# SN74HC165_Shift-In_Breakout-v12.net
KiCad netlist of a schematic drawn in EAGLE
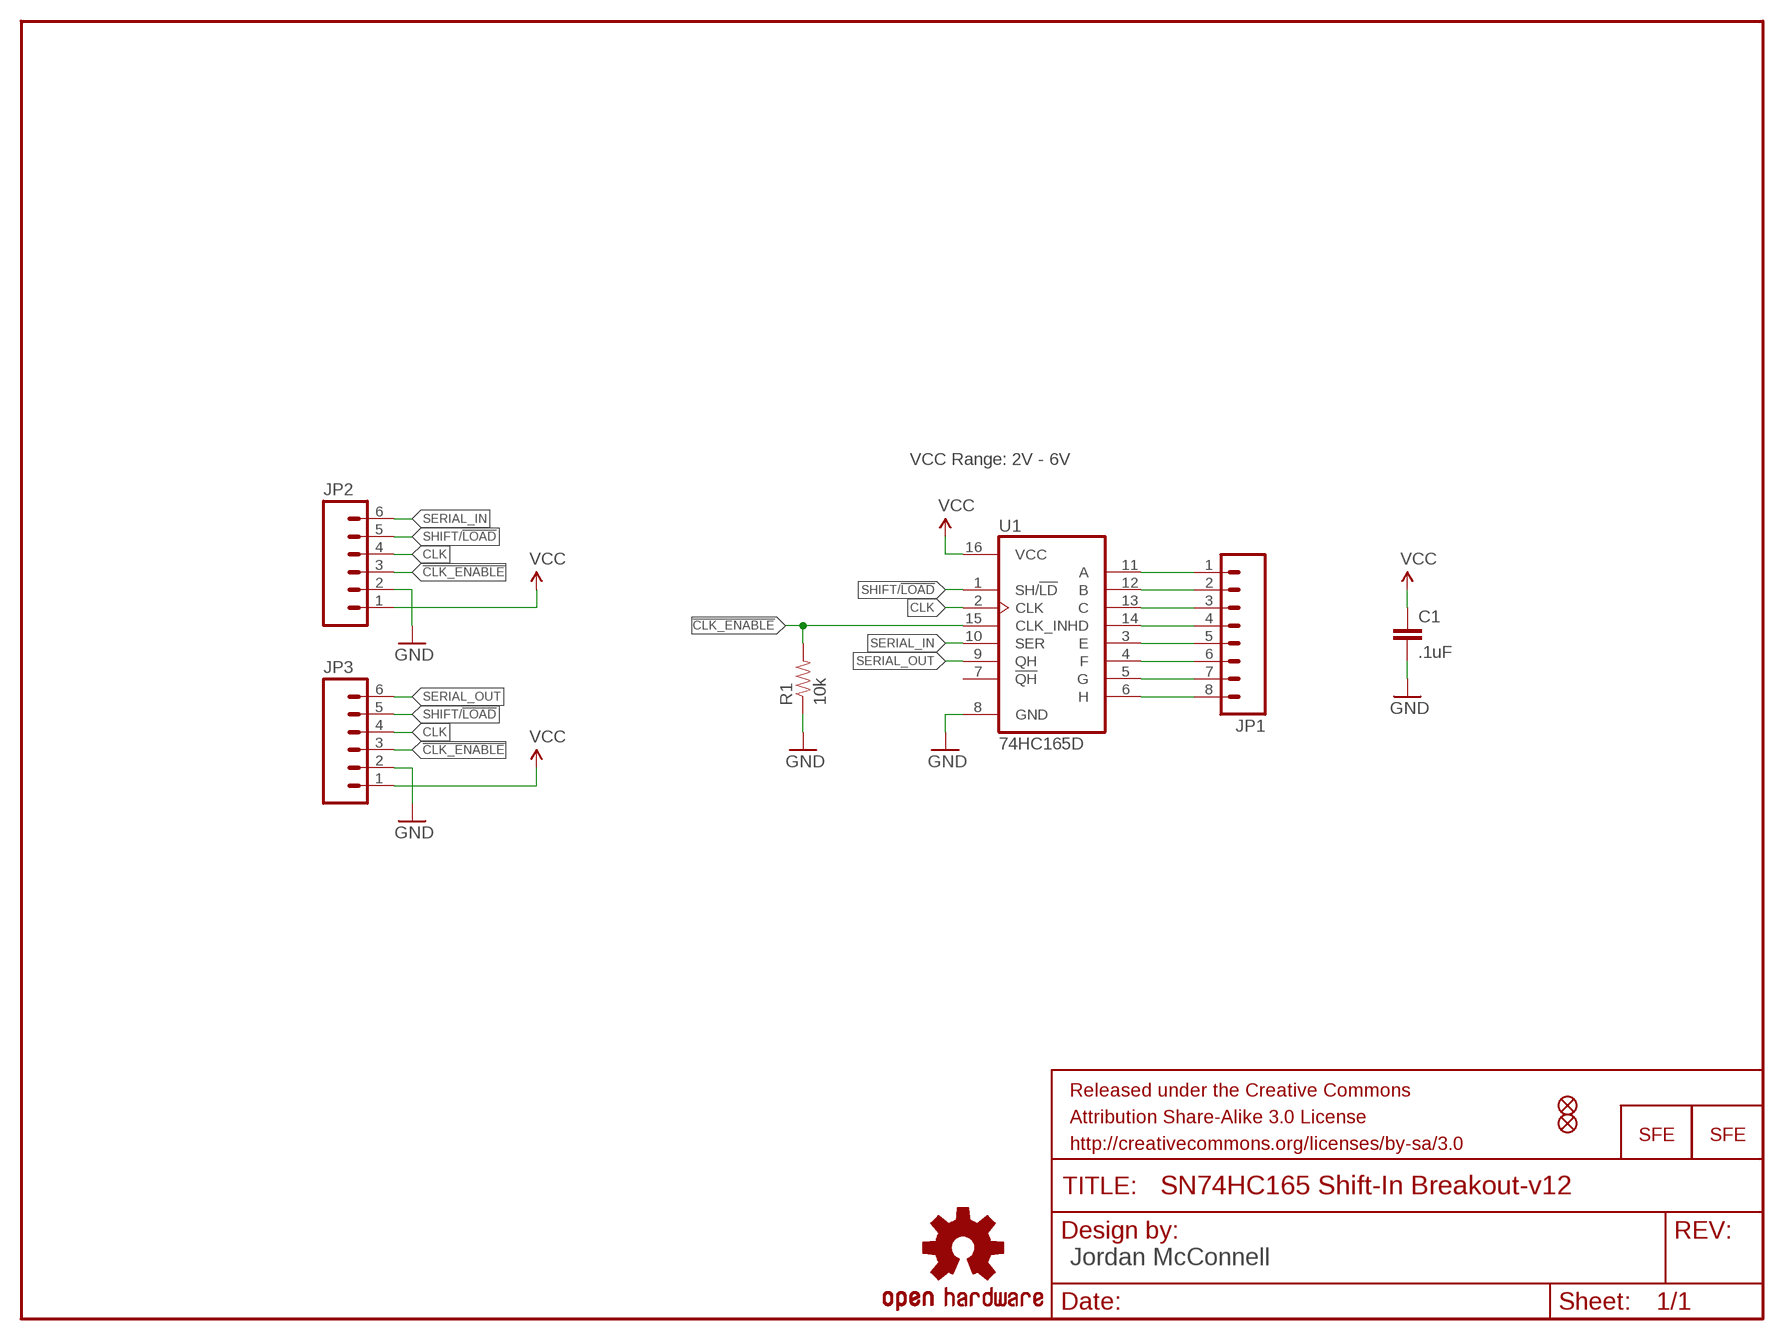
[diagram p0: schematic, sheet 1]

(export (version "E")
  (design (tool "Eeschema 10.0.6"))
  (components
    (comp (ref "C1")
      (value ".1uF")
      (footprint "eagle-import:0402-CAP")
      (libsource (lib "eagle-import") (part "CAP0402-CAP"))
    )
    (comp (ref "FRAME1")
      (value "FRAME-LETTER")
      (footprint "eagle-import:CREATIVE_COMMONS")
      (libsource (lib "eagle-import") (part "FRAME-LETTER"))
    )
    (comp (ref "JP1")
      (value "M081X08")
      (footprint "eagle-import:1X08")
      (libsource (lib "eagle-import") (part "M081X08"))
    )
    (comp (ref "JP2")
      (value "M06SIP")
      (footprint "eagle-import:1X06")
      (libsource (lib "eagle-import") (part "M06SIP"))
    )
    (comp (ref "JP3")
      (value "M06SIP")
      (footprint "eagle-import:1X06")
      (libsource (lib "eagle-import") (part "M06SIP"))
    )
    (comp (ref "JP4")
      (value "LOGO-SFESK")
      (footprint "eagle-import:SFE-LOGO-FLAME")
      (libsource (lib "eagle-import") (part "LOGO-SFESK"))
    )
    (comp (ref "JP5")
      (value "LOGO-SFENEW")
      (footprint "eagle-import:SFE-NEW-WEBLOGO")
      (libsource (lib "eagle-import") (part "LOGO-SFENEW"))
    )
    (comp (ref "JP6")
      (value "FIDUCIALUFIDUCIAL")
      (footprint "eagle-import:MICRO-FIDUCIAL")
      (libsource (lib "eagle-import") (part "FIDUCIALUFIDUCIAL"))
    )
    (comp (ref "JP7")
      (value "FIDUCIALUFIDUCIAL")
      (footprint "eagle-import:MICRO-FIDUCIAL")
      (libsource (lib "eagle-import") (part "FIDUCIALUFIDUCIAL"))
    )
    (comp (ref "R1")
      (value "10k")
      (footprint "eagle-import:0402-RES")
      (libsource (lib "eagle-import") (part "RESISTOR0402-RES"))
    )
    (comp (ref "U$1")
      (value "OSHW-LOGOS")
      (footprint "eagle-import:OSHW-LOGO-S")
      (libsource (lib "eagle-import") (part "OSHW-LOGOS"))
    )
    (comp (ref "U1")
      (value "74HC165D")
      (footprint "eagle-import:SO16")
      (libsource (lib "eagle-import") (part "74165D"))
    )
  )
  (nets
    (net (code "1") (name "/SHIFT{slash}~{LOAD}") (class "Default")
      (node (ref "JP2") (pin "5") (pinfunction "5_5") (pintype "passive"))
      (node (ref "JP3") (pin "5") (pinfunction "5_5") (pintype "passive"))
      (node (ref "U1") (pin "1") (pinfunction "SH/~{LD}_1") (pintype "input"))
    )
    (net (code "2") (name "/~{CLK_ENABLE}") (class "Default")
      (node (ref "JP2") (pin "3") (pinfunction "3_3") (pintype "passive"))
      (node (ref "JP3") (pin "3") (pinfunction "3_3") (pintype "passive"))
      (node (ref "R1") (pin "2") (pinfunction "2_2") (pintype "passive"))
      (node (ref "U1") (pin "15") (pinfunction "CLK_INH_15") (pintype "input"))
    )
    (net (code "3") (name "CLK") (class "Default")
      (node (ref "JP2") (pin "4") (pinfunction "4_4") (pintype "passive"))
      (node (ref "JP3") (pin "4") (pinfunction "4_4") (pintype "passive"))
      (node (ref "U1") (pin "2") (pinfunction "CLK_2") (pintype "input"))
    )
    (net (code "4") (name "GND") (class "Default")
      (node (ref "C1") (pin "2") (pinfunction "2_2") (pintype "passive"))
      (node (ref "JP2") (pin "2") (pinfunction "2_2") (pintype "passive"))
      (node (ref "JP3") (pin "2") (pinfunction "2_2") (pintype "passive"))
      (node (ref "R1") (pin "1") (pinfunction "1_1") (pintype "passive"))
      (node (ref "U1") (pin "8") (pinfunction "GND_8") (pintype "power_in"))
    )
    (net (code "5") (name "Net-(U1-A)") (class "Default")
      (node (ref "JP1") (pin "1") (pinfunction "1_1") (pintype "passive"))
      (node (ref "U1") (pin "11") (pinfunction "A_11") (pintype "tri_state"))
    )
    (net (code "6") (name "Net-(U1-B)") (class "Default")
      (node (ref "JP1") (pin "2") (pinfunction "2_2") (pintype "passive"))
      (node (ref "U1") (pin "12") (pinfunction "B_12") (pintype "tri_state"))
    )
    (net (code "7") (name "Net-(U1-C)") (class "Default")
      (node (ref "JP1") (pin "3") (pinfunction "3_3") (pintype "passive"))
      (node (ref "U1") (pin "13") (pinfunction "C_13") (pintype "tri_state"))
    )
    (net (code "8") (name "Net-(U1-D)") (class "Default")
      (node (ref "JP1") (pin "4") (pinfunction "4_4") (pintype "passive"))
      (node (ref "U1") (pin "14") (pinfunction "D_14") (pintype "tri_state"))
    )
    (net (code "9") (name "Net-(U1-E)") (class "Default")
      (node (ref "JP1") (pin "5") (pinfunction "5_5") (pintype "passive"))
      (node (ref "U1") (pin "3") (pinfunction "E_3") (pintype "tri_state"))
    )
    (net (code "10") (name "Net-(U1-F)") (class "Default")
      (node (ref "JP1") (pin "6") (pinfunction "6_6") (pintype "passive"))
      (node (ref "U1") (pin "4") (pinfunction "F_4") (pintype "tri_state"))
    )
    (net (code "11") (name "Net-(U1-G)") (class "Default")
      (node (ref "JP1") (pin "7") (pinfunction "7_7") (pintype "passive"))
      (node (ref "U1") (pin "5") (pinfunction "G_5") (pintype "tri_state"))
    )
    (net (code "12") (name "Net-(U1-H)") (class "Default")
      (node (ref "JP1") (pin "8") (pinfunction "8_8") (pintype "passive"))
      (node (ref "U1") (pin "6") (pinfunction "H_6") (pintype "tri_state"))
    )
    (net (code "13") (name "SERIAL_IN") (class "Default")
      (node (ref "JP2") (pin "6") (pinfunction "6_6") (pintype "passive"))
      (node (ref "U1") (pin "10") (pinfunction "SER_10") (pintype "input"))
    )
    (net (code "14") (name "SERIAL_OUT") (class "Default")
      (node (ref "JP3") (pin "6") (pinfunction "6_6") (pintype "passive"))
      (node (ref "U1") (pin "9") (pinfunction "QH_9") (pintype "tri_state"))
    )
    (net (code "15") (name "VCC") (class "Default")
      (node (ref "C1") (pin "1") (pinfunction "1_1") (pintype "passive"))
      (node (ref "JP2") (pin "1") (pinfunction "1_1") (pintype "passive"))
      (node (ref "JP3") (pin "1") (pinfunction "1_1") (pintype "passive"))
      (node (ref "U1") (pin "16") (pinfunction "VCC_16") (pintype "power_in"))
    )
    (net (code "16") (name "unconnected-(U1-~{QH}-Pad7)") (class "Default")
      (node (ref "U1") (pin "7") (pinfunction "~{QH}_7") (pintype "input"))
    )
  )
)
